# MRCS-Tiny85-Servo-Auto.net
KiCad netlist of a schematic drawn in EAGLE
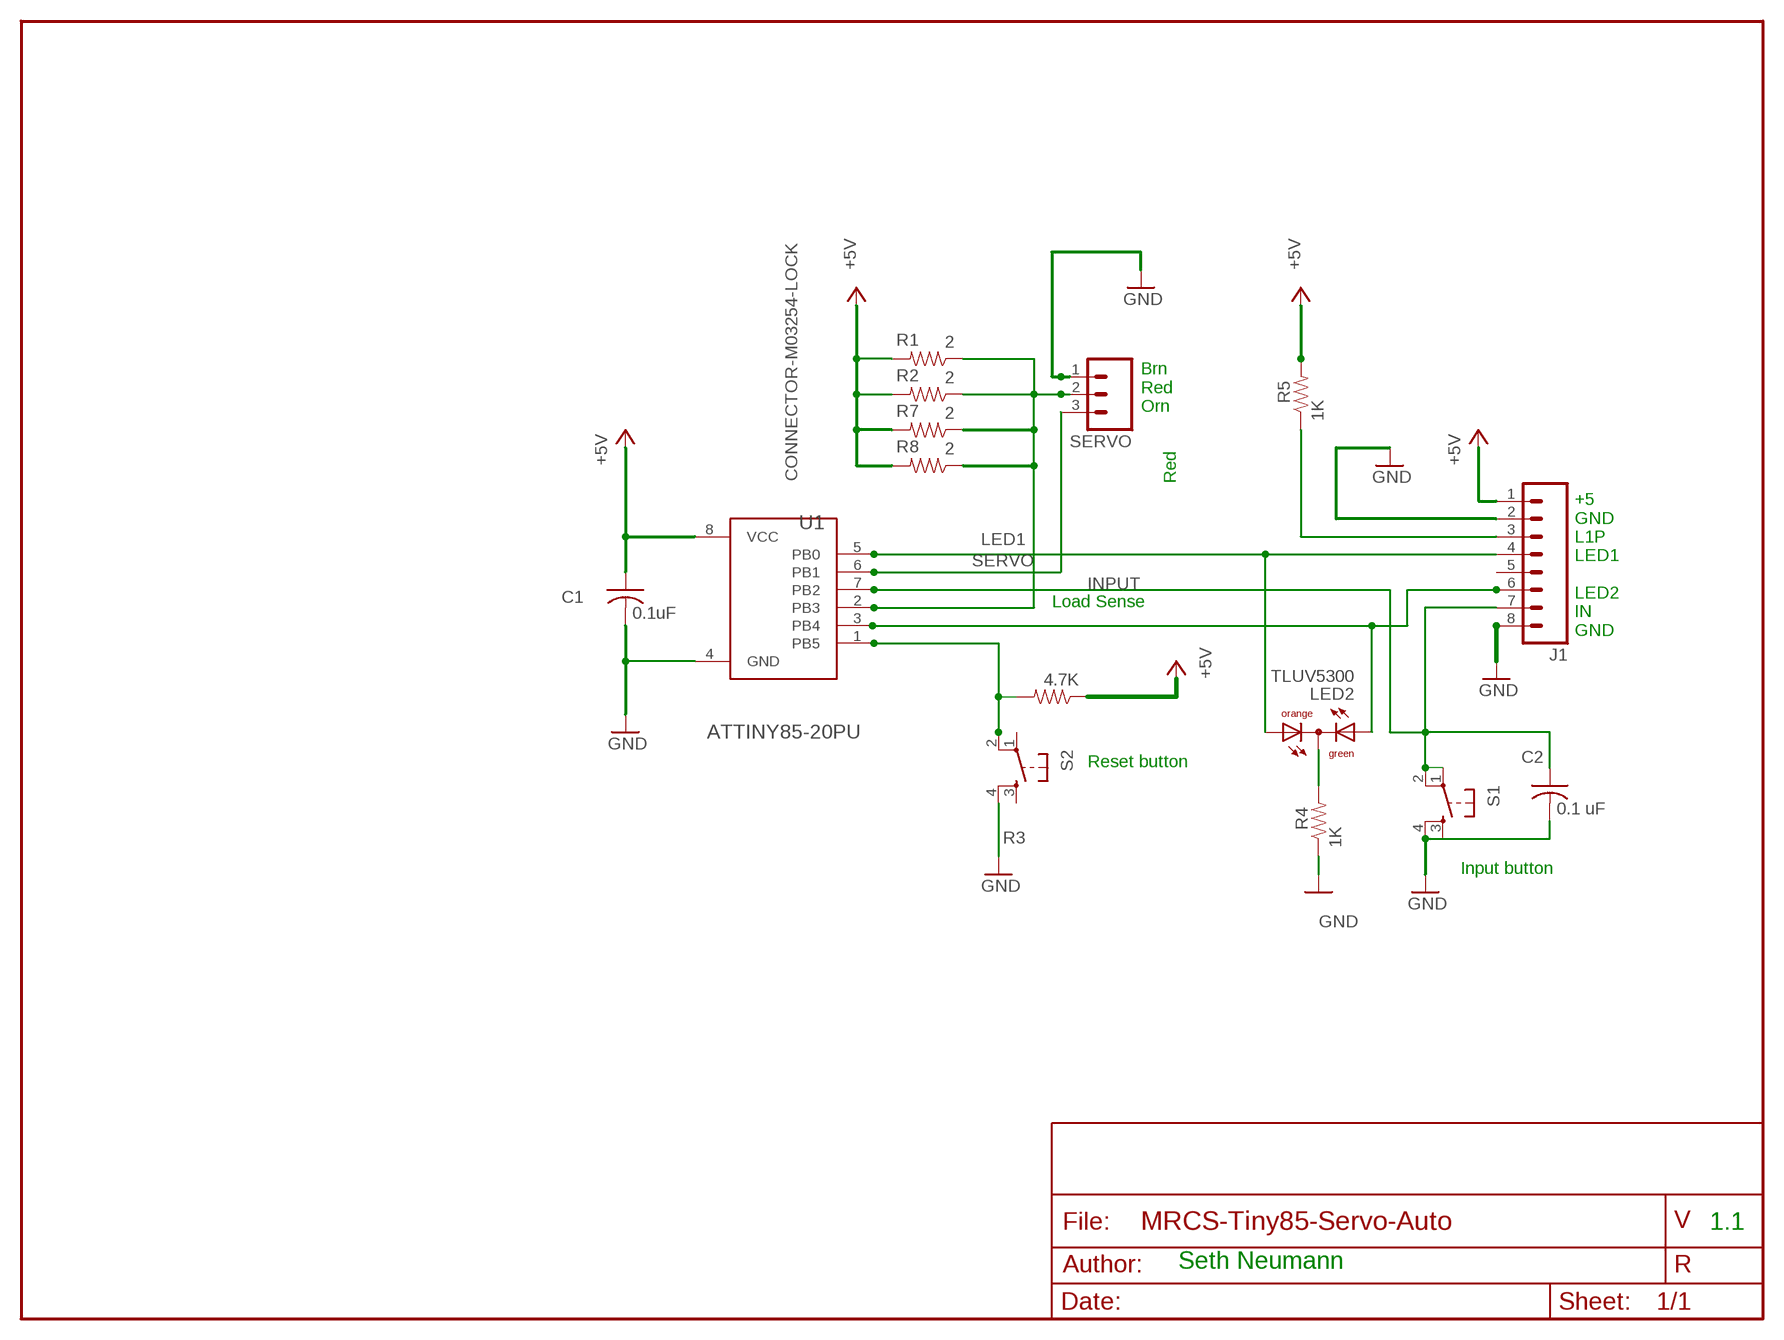
[diagram p0: schematic, sheet 1]

(export (version "E")
  (design (tool "Eeschema 10.0.6"))
  (components
    (comp (ref "C1")
      (value "0.1uF")
      (footprint "eagle-import:C-PTH-0.100")
      (libsource (lib "eagle-import") (part "CAPPTH2"))
    )
    (comp (ref "C2")
      (value "0.1 uF")
      (footprint "eagle-import:C-PTH-0.100")
      (libsource (lib "eagle-import") (part "CAPPTH2"))
    )
    (comp (ref "J1")
      (value "CONNECTOR-M08LOCK")
      (footprint "eagle-import:1X08_LOCK")
      (libsource (lib "eagle-import") (part "CONNECTOR-M08LOCK"))
    )
    (comp (ref "LED2")
      (value "TLUV5300")
      (footprint "eagle-import:TLUV5300")
      (libsource (lib "eagle-import") (part "TLUV5300"))
    )
    (comp (ref "R1")
      (value "2")
      (footprint "eagle-import:AXIAL-0.4-RES")
      (libsource (lib "eagle-import") (part "RPTH04"))
    )
    (comp (ref "R2")
      (value "2")
      (footprint "eagle-import:AXIAL-0.4-RES")
      (libsource (lib "eagle-import") (part "RPTH04"))
    )
    (comp (ref "R3")
      (value "4.7K")
      (footprint "eagle-import:AXIAL-0.4-RES")
      (libsource (lib "eagle-import") (part "RPTH04"))
    )
    (comp (ref "R4")
      (value "1K")
      (footprint "eagle-import:AXIAL-0.4-RES")
      (libsource (lib "eagle-import") (part "RPTH04"))
    )
    (comp (ref "R5")
      (value "1K")
      (footprint "eagle-import:AXIAL-0.4-RES")
      (libsource (lib "eagle-import") (part "RPTH04"))
    )
    (comp (ref "R7")
      (value "2")
      (footprint "eagle-import:AXIAL-0.4-RES")
      (libsource (lib "eagle-import") (part "RPTH04"))
    )
    (comp (ref "R8")
      (value "2")
      (footprint "eagle-import:AXIAL-0.4-RES")
      (libsource (lib "eagle-import") (part "RPTH04"))
    )
    (comp (ref "S1")
      (value "TAC_SWITCHPTH")
      (footprint "eagle-import:TACTILE-PTH")
      (libsource (lib "eagle-import") (part "TAC_SWITCHPTH"))
    )
    (comp (ref "S2")
      (value "TAC_SWITCHPTH")
      (footprint "eagle-import:TACTILE-PTH")
      (libsource (lib "eagle-import") (part "TAC_SWITCHPTH"))
    )
    (comp (ref "SERVO")
      (value "CONNECTOR-M03254-LOCK")
      (footprint "eagle-import:3POL254")
      (libsource (lib "eagle-import") (part "CONNECTOR-M03254-LOCK"))
    )
    (comp (ref "U1")
      (value "ATTINY85-20PU")
      (footprint "eagle-import:DIP762W46P254L927H533Q8B")
      (fields (field (name "MF") "Microchip Technology / Atmel"))
      (libsource (lib "eagle-import") (part "ATTINY85-20PU"))
    )
  )
  (nets
    (net (code "1") (name "+5V") (class "Default")
      (node (ref "C1") (pin "1") (pinfunction "1_1") (pintype "passive"))
      (node (ref "J1") (pin "1") (pinfunction "1_1") (pintype "passive"))
      (node (ref "R1") (pin "P$2") (pinfunction "2_P$2") (pintype "passive"))
      (node (ref "R2") (pin "P$2") (pinfunction "2_P$2") (pintype "passive"))
      (node (ref "R3") (pin "P$1") (pinfunction "1_P$1") (pintype "passive"))
      (node (ref "R5") (pin "P$2") (pinfunction "2_P$2") (pintype "passive"))
      (node (ref "R7") (pin "P$2") (pinfunction "2_P$2") (pintype "passive"))
      (node (ref "R8") (pin "P$2") (pinfunction "2_P$2") (pintype "passive"))
      (node (ref "U1") (pin "8") (pinfunction "VCC_8") (pintype "power_in"))
    )
    (net (code "2") (name "/INPUT") (class "Default")
      (node (ref "C2") (pin "1") (pinfunction "1_1") (pintype "passive"))
      (node (ref "J1") (pin "7") (pinfunction "7_7") (pintype "passive"))
      (node (ref "S1") (pin "1") (pinfunction "1_1") (pintype "passive"))
      (node (ref "S1") (pin "2") (pinfunction "2_2") (pintype "passive"))
      (node (ref "U1") (pin "7") (pinfunction "PB2_7") (pintype "bidirectional"))
    )
    (net (code "3") (name "/LED1") (class "Default")
      (node (ref "J1") (pin "4") (pinfunction "4_4") (pintype "passive"))
      (node (ref "LED2") (pin "AO") (pinfunction "AO_AO") (pintype "passive"))
      (node (ref "U1") (pin "5") (pinfunction "PB0_5") (pintype "bidirectional"))
    )
    (net (code "4") (name "/SERVO") (class "Default")
      (node (ref "SERVO") (pin "3") (pinfunction "3_3") (pintype "passive"))
      (node (ref "U1") (pin "6") (pinfunction "PB1_6") (pintype "bidirectional"))
    )
    (net (code "5") (name "GND") (class "Default")
      (node (ref "C1") (pin "2") (pinfunction "2_2") (pintype "passive"))
      (node (ref "C2") (pin "2") (pinfunction "2_2") (pintype "passive"))
      (node (ref "J1") (pin "2") (pinfunction "2_2") (pintype "passive"))
      (node (ref "J1") (pin "8") (pinfunction "8_8") (pintype "passive"))
      (node (ref "R4") (pin "P$1") (pinfunction "1_P$1") (pintype "passive"))
      (node (ref "S1") (pin "3") (pinfunction "3_3") (pintype "passive"))
      (node (ref "S1") (pin "4") (pinfunction "4_4") (pintype "passive"))
      (node (ref "S2") (pin "4") (pinfunction "4_4") (pintype "passive"))
      (node (ref "SERVO") (pin "1") (pinfunction "1_1") (pintype "passive"))
      (node (ref "U1") (pin "4") (pinfunction "GND_4") (pintype "power_in"))
    )
    (net (code "6") (name "Net-(R1-1)") (class "Default")
      (node (ref "R1") (pin "P$1") (pinfunction "1_P$1") (pintype "passive"))
      (node (ref "R2") (pin "P$1") (pinfunction "1_P$1") (pintype "passive"))
      (node (ref "R7") (pin "P$1") (pinfunction "1_P$1") (pintype "passive"))
      (node (ref "R8") (pin "P$1") (pinfunction "1_P$1") (pintype "passive"))
      (node (ref "SERVO") (pin "2") (pinfunction "2_2") (pintype "passive"))
      (node (ref "U1") (pin "2") (pinfunction "PB3_2") (pintype "bidirectional"))
    )
    (net (code "7") (name "Net-(R3-2)") (class "Default")
      (node (ref "R3") (pin "P$2") (pinfunction "2_P$2") (pintype "passive"))
      (node (ref "S2") (pin "2") (pinfunction "2_2") (pintype "passive"))
      (node (ref "U1") (pin "1") (pinfunction "PB5_1") (pintype "bidirectional"))
    )
    (net (code "8") (name "Net-(R4-2)") (class "Default")
      (node (ref "LED2") (pin "CC") (pinfunction "CC_CC") (pintype "passive"))
      (node (ref "R4") (pin "P$2") (pinfunction "2_P$2") (pintype "passive"))
    )
    (net (code "9") (name "Net-(R5-1)") (class "Default")
      (node (ref "J1") (pin "3") (pinfunction "3_3") (pintype "passive"))
      (node (ref "R5") (pin "P$1") (pinfunction "1_P$1") (pintype "passive"))
    )
    (net (code "10") (name "Net-(U1-PB4)") (class "Default")
      (node (ref "J1") (pin "6") (pinfunction "6_6") (pintype "passive"))
      (node (ref "LED2") (pin "AG") (pinfunction "AG_AG") (pintype "passive"))
      (node (ref "U1") (pin "3") (pinfunction "PB4_3") (pintype "bidirectional"))
    )
    (net (code "11") (name "unconnected-(J1-Pad5)") (class "Default")
      (node (ref "J1") (pin "5") (pinfunction "5_5") (pintype "passive"))
    )
    (net (code "12") (name "unconnected-(S2-Pad1)") (class "Default")
      (node (ref "S2") (pin "1") (pinfunction "1_1") (pintype "passive"))
    )
    (net (code "13") (name "unconnected-(S2-Pad3)") (class "Default")
      (node (ref "S2") (pin "3") (pinfunction "3_3") (pintype "passive"))
    )
  )
)
